# level_switch.net
KiCad netlist of a schematic drawn in Altium Designer
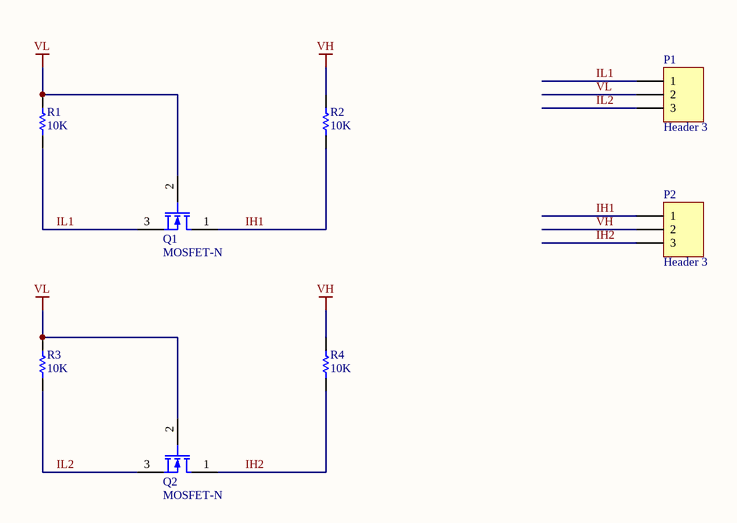
[diagram p0: level_switch.SchDoc]

(export (version "E")
  (design (tool "Eeschema 10.0.6"))
  (components
    (comp (ref "P1")
      (value "Header 3")
      (footprint "HDR1X3")
      (description "Header, 3-Pin")
      (fields (field (name "PUBLISHER") "Altium Limited"))
      (libsource (lib "Miscellaneous Connectors") (part "Header 3"))
    )
    (comp (ref "P2")
      (value "Header 3")
      (footprint "HDR1X3")
      (description "Header, 3-Pin")
      (fields (field (name "PUBLISHER") "Altium Limited"))
      (libsource (lib "Miscellaneous Connectors") (part "Header 3"))
    )
    (comp (ref "Q1")
      (value "MOSFET-N")
      (footprint "SOT23-3-MOS")
      (description "N-Channel MOSFET")
      (fields (field (name "PUBLISHER") "Altium Limited"))
      (libsource (lib "Miscellaneous Devices") (part "MOSFET-N"))
    )
    (comp (ref "Q2")
      (value "MOSFET-N")
      (footprint "SOT23-3-MOS")
      (description "N-Channel MOSFET")
      (fields (field (name "PUBLISHER") "Altium Limited"))
      (libsource (lib "Miscellaneous Devices") (part "MOSFET-N"))
    )
    (comp (ref "R1")
      (value "10K")
      (footprint "R0603")
      (description "Resistor")
      (fields (field (name "Comment") "Res1") (field (name "PUBLISHER") "Altium Limited"))
      (libsource (lib "Miscellaneous Devices") (part "Res1"))
    )
    (comp (ref "R2")
      (value "10K")
      (footprint "R0603")
      (description "Resistor")
      (fields (field (name "Comment") "Res1") (field (name "PUBLISHER") "Altium Limited"))
      (libsource (lib "Miscellaneous Devices") (part "Res1"))
    )
    (comp (ref "R3")
      (value "10K")
      (footprint "R0603")
      (description "Resistor")
      (fields (field (name "Comment") "Res1") (field (name "PUBLISHER") "Altium Limited"))
      (libsource (lib "Miscellaneous Devices") (part "Res1"))
    )
    (comp (ref "R4")
      (value "10K")
      (footprint "R0603")
      (description "Resistor")
      (fields (field (name "Comment") "Res1") (field (name "PUBLISHER") "Altium Limited"))
      (libsource (lib "Miscellaneous Devices") (part "Res1"))
    )
  )
  (nets
    (net (code "1") (name "/IH1") (class "Default")
      (node (ref "P2") (pin "1") (pinfunction "1_1") (pintype "passive"))
      (node (ref "Q1") (pin "1") (pinfunction "D_1") (pintype "passive"))
      (node (ref "R2") (pin "1") (pinfunction "1_1") (pintype "passive"))
    )
    (net (code "2") (name "/IH2") (class "Default")
      (node (ref "P2") (pin "3") (pinfunction "3_3") (pintype "passive"))
      (node (ref "Q2") (pin "1") (pinfunction "D_1") (pintype "passive"))
      (node (ref "R4") (pin "1") (pinfunction "1_1") (pintype "passive"))
    )
    (net (code "3") (name "/IL1") (class "Default")
      (node (ref "P1") (pin "1") (pinfunction "1_1") (pintype "passive"))
      (node (ref "Q1") (pin "3") (pinfunction "S_3") (pintype "passive"))
      (node (ref "R1") (pin "1") (pinfunction "1_1") (pintype "passive"))
    )
    (net (code "4") (name "/IL2") (class "Default")
      (node (ref "P1") (pin "3") (pinfunction "3_3") (pintype "passive"))
      (node (ref "Q2") (pin "3") (pinfunction "S_3") (pintype "passive"))
      (node (ref "R3") (pin "1") (pinfunction "1_1") (pintype "passive"))
    )
    (net (code "5") (name "VH") (class "Default")
      (node (ref "P2") (pin "2") (pinfunction "2_2") (pintype "passive"))
      (node (ref "R2") (pin "2") (pinfunction "2_2") (pintype "passive"))
      (node (ref "R4") (pin "2") (pinfunction "2_2") (pintype "passive"))
    )
    (net (code "6") (name "VL") (class "Default")
      (node (ref "P1") (pin "2") (pinfunction "2_2") (pintype "passive"))
      (node (ref "Q1") (pin "2") (pinfunction "G_2") (pintype "passive"))
      (node (ref "Q2") (pin "2") (pinfunction "G_2") (pintype "passive"))
      (node (ref "R1") (pin "2") (pinfunction "2_2") (pintype "passive"))
      (node (ref "R3") (pin "2") (pinfunction "2_2") (pintype "passive"))
    )
  )
)
